# ZB3.net
KiCad netlist of a schematic drawn in Altium Designer
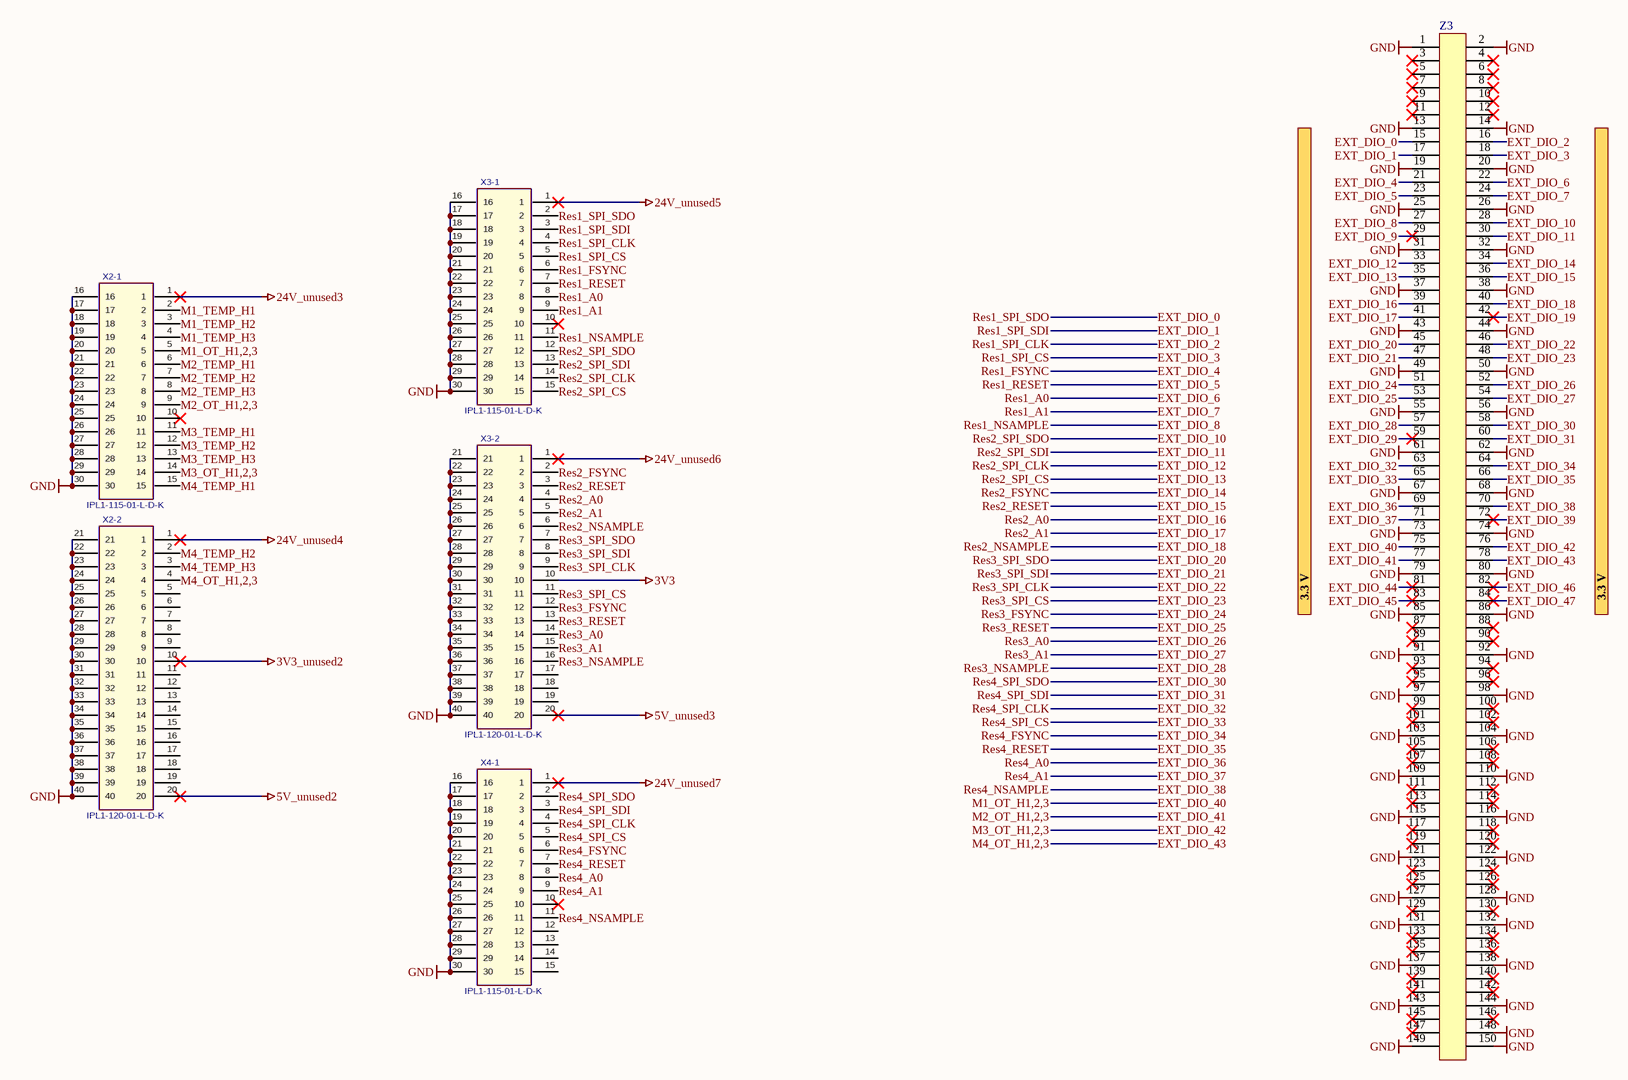
[diagram p0: ZB3.SchDoc]

(export (version "E")
  (design (tool "Eeschema 10.0.6"))
  (components
    (comp (ref "X2-1")
      (value "IPL1-115-01-L-D-K")
      (footprint "IPL1-115-01-YYY-D-K")
      (description "2.54 mm Double Row Terminal Assembly")
      (fields
        (field (name "MANUFACTURER") "SAMTEC")
        (field (name "LCSC PART NUMBER") "C17431809")
        (field (name "CREATED FROM") "MGremer")
      )
      (libsource (lib "user") (part "IPL1-115-01-XX-D-XX"))
    )
    (comp (ref "X2-2")
      (value "IPL1-120-01-L-D-K")
      (footprint "SAMTEC_IPL1-120-01-X-D-K")
      (description "Terminal Assembly, Double Row, Thru-Hole, 2.54 mm x 2.54 mm Pitch, 40 Pins")
      (fields
        (field (name "MANUFACTURER") "SAMTEC")
        (field (name "LCSC PART NUMBER") "C17429670")
        (field (name "CREATED FROM") "PBaumann")
      )
      (libsource (lib "user") (part "IPL1-120-01-XX-D-XX"))
    )
    (comp (ref "X3-1")
      (value "IPL1-115-01-L-D-K")
      (footprint "IPL1-115-01-YYY-D-K")
      (description "2.54 mm Double Row Terminal Assembly")
      (fields
        (field (name "MANUFACTURER") "SAMTEC")
        (field (name "LCSC PART NUMBER") "C17431809")
        (field (name "CREATED FROM") "MGremer")
      )
      (libsource (lib "user") (part "IPL1-115-01-XX-D-XX"))
    )
    (comp (ref "X3-2")
      (value "IPL1-120-01-L-D-K")
      (footprint "SAMTEC_IPL1-120-01-X-D-K")
      (description "Terminal Assembly, Double Row, Thru-Hole, 2.54 mm x 2.54 mm Pitch, 40 Pins")
      (fields
        (field (name "MANUFACTURER") "SAMTEC")
        (field (name "LCSC PART NUMBER") "C17429670")
        (field (name "CREATED FROM") "PBaumann")
      )
      (libsource (lib "user") (part "IPL1-120-01-XX-D-XX"))
    )
    (comp (ref "X4-1")
      (value "IPL1-115-01-L-D-K")
      (footprint "IPL1-115-01-YYY-D-K")
      (description "2.54 mm Double Row Terminal Assembly")
      (fields
        (field (name "MANUFACTURER") "SAMTEC")
        (field (name "LCSC PART NUMBER") "C17431809")
        (field (name "CREATED FROM") "MGremer")
      )
      (libsource (lib "user") (part "IPL1-115-01-XX-D-XX"))
    )
    (comp (ref "Z3")
      (value "~")
      (footprint "ERM8-075-02.0-L-DV")
      (description "0.80 mm Edge Rate Rugged High Speed")
      (fields
        (field (name "MANUFACTURER PART NUMBER") "ERM8-075-02.0-L-DV-TR")
        (field (name "MANUFACTURER") "SAMTEC")
        (field (name "CREATED FROM") "AGeiger")
      )
      (libsource (lib "user") (part "CON-150"))
    )
  )
  (nets
    (net (code "1") (name "/EXT_DIO_0") (class "Default")
      (node (ref "X3-1") (pin "2") (pinfunction "2_2") (pintype "passive"))
      (node (ref "Z3") (pin "15") (pinfunction "15_15") (pintype "passive"))
    )
    (net (code "2") (name "/EXT_DIO_1") (class "Default")
      (node (ref "X3-1") (pin "3") (pinfunction "3_3") (pintype "passive"))
      (node (ref "Z3") (pin "17") (pinfunction "17_17") (pintype "passive"))
    )
    (net (code "3") (name "/EXT_DIO_2") (class "Default")
      (node (ref "X3-1") (pin "4") (pinfunction "4_4") (pintype "passive"))
      (node (ref "Z3") (pin "16") (pinfunction "16_16") (pintype "passive"))
    )
    (net (code "4") (name "/EXT_DIO_3") (class "Default")
      (node (ref "X3-1") (pin "5") (pinfunction "5_5") (pintype "passive"))
      (node (ref "Z3") (pin "18") (pinfunction "18_18") (pintype "passive"))
    )
    (net (code "5") (name "/EXT_DIO_4") (class "Default")
      (node (ref "X3-1") (pin "6") (pinfunction "6_6") (pintype "passive"))
      (node (ref "Z3") (pin "21") (pinfunction "21_21") (pintype "passive"))
    )
    (net (code "6") (name "/EXT_DIO_5") (class "Default")
      (node (ref "X3-1") (pin "7") (pinfunction "7_7") (pintype "passive"))
      (node (ref "Z3") (pin "23") (pinfunction "23_23") (pintype "passive"))
    )
    (net (code "7") (name "/EXT_DIO_6") (class "Default")
      (node (ref "X3-1") (pin "8") (pinfunction "8_8") (pintype "passive"))
      (node (ref "Z3") (pin "22") (pinfunction "22_22") (pintype "passive"))
    )
    (net (code "8") (name "/EXT_DIO_7") (class "Default")
      (node (ref "X3-1") (pin "9") (pinfunction "9_9") (pintype "passive"))
      (node (ref "Z3") (pin "24") (pinfunction "24_24") (pintype "passive"))
    )
    (net (code "9") (name "/EXT_DIO_8") (class "Default")
      (node (ref "X3-1") (pin "11") (pinfunction "11_11") (pintype "passive"))
      (node (ref "Z3") (pin "27") (pinfunction "27_27") (pintype "passive"))
    )
    (net (code "10") (name "/EXT_DIO_9") (class "Default")
      (node (ref "Z3") (pin "29") (pinfunction "29_29") (pintype "passive+no_connect"))
    )
    (net (code "11") (name "/EXT_DIO_10") (class "Default")
      (node (ref "X3-1") (pin "12") (pinfunction "12_12") (pintype "passive"))
      (node (ref "Z3") (pin "28") (pinfunction "28_28") (pintype "passive"))
    )
    (net (code "12") (name "/EXT_DIO_11") (class "Default")
      (node (ref "X3-1") (pin "13") (pinfunction "13_13") (pintype "passive"))
      (node (ref "Z3") (pin "30") (pinfunction "30_30") (pintype "passive"))
    )
    (net (code "13") (name "/EXT_DIO_12") (class "Default")
      (node (ref "X3-1") (pin "14") (pinfunction "14_14") (pintype "passive"))
      (node (ref "Z3") (pin "33") (pinfunction "33_33") (pintype "passive"))
    )
    (net (code "14") (name "/EXT_DIO_13") (class "Default")
      (node (ref "X3-1") (pin "15") (pinfunction "15_15") (pintype "passive"))
      (node (ref "Z3") (pin "35") (pinfunction "35_35") (pintype "passive"))
    )
    (net (code "15") (name "/EXT_DIO_14") (class "Default")
      (node (ref "X3-2") (pin "2") (pinfunction "2_2") (pintype "passive"))
      (node (ref "Z3") (pin "34") (pinfunction "34_34") (pintype "passive"))
    )
    (net (code "16") (name "/EXT_DIO_15") (class "Default")
      (node (ref "X3-2") (pin "3") (pinfunction "3_3") (pintype "passive"))
      (node (ref "Z3") (pin "36") (pinfunction "36_36") (pintype "passive"))
    )
    (net (code "17") (name "/EXT_DIO_16") (class "Default")
      (node (ref "X3-2") (pin "4") (pinfunction "4_4") (pintype "passive"))
      (node (ref "Z3") (pin "39") (pinfunction "39_39") (pintype "passive"))
    )
    (net (code "18") (name "/EXT_DIO_17") (class "Default")
      (node (ref "X3-2") (pin "5") (pinfunction "5_5") (pintype "passive"))
      (node (ref "Z3") (pin "41") (pinfunction "41_41") (pintype "passive"))
    )
    (net (code "19") (name "/EXT_DIO_18") (class "Default")
      (node (ref "X3-2") (pin "6") (pinfunction "6_6") (pintype "passive"))
      (node (ref "Z3") (pin "40") (pinfunction "40_40") (pintype "passive"))
    )
    (net (code "20") (name "/EXT_DIO_19") (class "Default")
      (node (ref "Z3") (pin "42") (pinfunction "42_42") (pintype "passive+no_connect"))
    )
    (net (code "21") (name "/EXT_DIO_20") (class "Default")
      (node (ref "X3-2") (pin "7") (pinfunction "7_7") (pintype "passive"))
      (node (ref "Z3") (pin "45") (pinfunction "45_45") (pintype "passive"))
    )
    (net (code "22") (name "/EXT_DIO_21") (class "Default")
      (node (ref "X3-2") (pin "8") (pinfunction "8_8") (pintype "passive"))
      (node (ref "Z3") (pin "47") (pinfunction "47_47") (pintype "passive"))
    )
    (net (code "23") (name "/EXT_DIO_22") (class "Default")
      (node (ref "X3-2") (pin "9") (pinfunction "9_9") (pintype "passive"))
      (node (ref "Z3") (pin "46") (pinfunction "46_46") (pintype "passive"))
    )
    (net (code "24") (name "/EXT_DIO_23") (class "Default")
      (node (ref "X3-2") (pin "11") (pinfunction "11_11") (pintype "passive"))
      (node (ref "Z3") (pin "48") (pinfunction "48_48") (pintype "passive"))
    )
    (net (code "25") (name "/EXT_DIO_24") (class "Default")
      (node (ref "X3-2") (pin "12") (pinfunction "12_12") (pintype "passive"))
      (node (ref "Z3") (pin "51") (pinfunction "51_51") (pintype "passive"))
    )
    (net (code "26") (name "/EXT_DIO_25") (class "Default")
      (node (ref "X3-2") (pin "13") (pinfunction "13_13") (pintype "passive"))
      (node (ref "Z3") (pin "53") (pinfunction "53_53") (pintype "passive"))
    )
    (net (code "27") (name "/EXT_DIO_26") (class "Default")
      (node (ref "X3-2") (pin "14") (pinfunction "14_14") (pintype "passive"))
      (node (ref "Z3") (pin "52") (pinfunction "52_52") (pintype "passive"))
    )
    (net (code "28") (name "/EXT_DIO_27") (class "Default")
      (node (ref "X3-2") (pin "15") (pinfunction "15_15") (pintype "passive"))
      (node (ref "Z3") (pin "54") (pinfunction "54_54") (pintype "passive"))
    )
    (net (code "29") (name "/EXT_DIO_28") (class "Default")
      (node (ref "X3-2") (pin "16") (pinfunction "16_16") (pintype "passive"))
      (node (ref "Z3") (pin "57") (pinfunction "57_57") (pintype "passive"))
    )
    (net (code "30") (name "/EXT_DIO_29") (class "Default")
      (node (ref "Z3") (pin "59") (pinfunction "59_59") (pintype "passive+no_connect"))
    )
    (net (code "31") (name "/EXT_DIO_30") (class "Default")
      (node (ref "X4-1") (pin "2") (pinfunction "2_2") (pintype "passive"))
      (node (ref "Z3") (pin "58") (pinfunction "58_58") (pintype "passive"))
    )
    (net (code "32") (name "/EXT_DIO_31") (class "Default")
      (node (ref "X4-1") (pin "3") (pinfunction "3_3") (pintype "passive"))
      (node (ref "Z3") (pin "60") (pinfunction "60_60") (pintype "passive"))
    )
    (net (code "33") (name "/EXT_DIO_32") (class "Default")
      (node (ref "X4-1") (pin "4") (pinfunction "4_4") (pintype "passive"))
      (node (ref "Z3") (pin "63") (pinfunction "63_63") (pintype "passive"))
    )
    (net (code "34") (name "/EXT_DIO_33") (class "Default")
      (node (ref "X4-1") (pin "5") (pinfunction "5_5") (pintype "passive"))
      (node (ref "Z3") (pin "65") (pinfunction "65_65") (pintype "passive"))
    )
    (net (code "35") (name "/EXT_DIO_34") (class "Default")
      (node (ref "X4-1") (pin "6") (pinfunction "6_6") (pintype "passive"))
      (node (ref "Z3") (pin "64") (pinfunction "64_64") (pintype "passive"))
    )
    (net (code "36") (name "/EXT_DIO_35") (class "Default")
      (node (ref "X4-1") (pin "7") (pinfunction "7_7") (pintype "passive"))
      (node (ref "Z3") (pin "66") (pinfunction "66_66") (pintype "passive"))
    )
    (net (code "37") (name "/EXT_DIO_36") (class "Default")
      (node (ref "X4-1") (pin "8") (pinfunction "8_8") (pintype "passive"))
      (node (ref "Z3") (pin "69") (pinfunction "69_69") (pintype "passive"))
    )
    (net (code "38") (name "/EXT_DIO_37") (class "Default")
      (node (ref "X4-1") (pin "9") (pinfunction "9_9") (pintype "passive"))
      (node (ref "Z3") (pin "71") (pinfunction "71_71") (pintype "passive"))
    )
    (net (code "39") (name "/EXT_DIO_38") (class "Default")
      (node (ref "X4-1") (pin "11") (pinfunction "11_11") (pintype "passive"))
      (node (ref "Z3") (pin "70") (pinfunction "70_70") (pintype "passive"))
    )
    (net (code "40") (name "/EXT_DIO_39") (class "Default")
      (node (ref "Z3") (pin "72") (pinfunction "72_72") (pintype "passive+no_connect"))
    )
    (net (code "41") (name "/EXT_DIO_40") (class "Default")
      (node (ref "X2-1") (pin "5") (pinfunction "5_5") (pintype "passive"))
      (node (ref "Z3") (pin "75") (pinfunction "75_75") (pintype "passive"))
    )
    (net (code "42") (name "/EXT_DIO_41") (class "Default")
      (node (ref "X2-1") (pin "9") (pinfunction "9_9") (pintype "passive"))
      (node (ref "Z3") (pin "77") (pinfunction "77_77") (pintype "passive"))
    )
    (net (code "43") (name "/EXT_DIO_42") (class "Default")
      (node (ref "X2-1") (pin "14") (pinfunction "14_14") (pintype "passive"))
      (node (ref "Z3") (pin "76") (pinfunction "76_76") (pintype "passive"))
    )
    (net (code "44") (name "/EXT_DIO_43") (class "Default")
      (node (ref "X2-2") (pin "4") (pinfunction "4_4") (pintype "passive"))
      (node (ref "Z3") (pin "78") (pinfunction "78_78") (pintype "passive"))
    )
    (net (code "45") (name "/EXT_DIO_44") (class "Default")
      (node (ref "Z3") (pin "81") (pinfunction "81_81") (pintype "passive+no_connect"))
    )
    (net (code "46") (name "/EXT_DIO_45") (class "Default")
      (node (ref "Z3") (pin "83") (pinfunction "83_83") (pintype "passive+no_connect"))
    )
    (net (code "47") (name "/EXT_DIO_46") (class "Default")
      (node (ref "Z3") (pin "82") (pinfunction "82_82") (pintype "passive+no_connect"))
    )
    (net (code "48") (name "/EXT_DIO_47") (class "Default")
      (node (ref "Z3") (pin "84") (pinfunction "84_84") (pintype "passive+no_connect"))
    )
    (net (code "49") (name "/M1_TEMP_H1") (class "Default")
      (node (ref "X2-1") (pin "2") (pinfunction "2_2") (pintype "passive"))
    )
    (net (code "50") (name "/M1_TEMP_H2") (class "Default")
      (node (ref "X2-1") (pin "3") (pinfunction "3_3") (pintype "passive"))
    )
    (net (code "51") (name "/M1_TEMP_H3") (class "Default")
      (node (ref "X2-1") (pin "4") (pinfunction "4_4") (pintype "passive"))
    )
    (net (code "52") (name "/M2_TEMP_H1") (class "Default")
      (node (ref "X2-1") (pin "6") (pinfunction "6_6") (pintype "passive"))
    )
    (net (code "53") (name "/M2_TEMP_H2") (class "Default")
      (node (ref "X2-1") (pin "7") (pinfunction "7_7") (pintype "passive"))
    )
    (net (code "54") (name "/M2_TEMP_H3") (class "Default")
      (node (ref "X2-1") (pin "8") (pinfunction "8_8") (pintype "passive"))
    )
    (net (code "55") (name "/M3_TEMP_H1") (class "Default")
      (node (ref "X2-1") (pin "11") (pinfunction "11_11") (pintype "passive"))
    )
    (net (code "56") (name "/M3_TEMP_H2") (class "Default")
      (node (ref "X2-1") (pin "12") (pinfunction "12_12") (pintype "passive"))
    )
    (net (code "57") (name "/M3_TEMP_H3") (class "Default")
      (node (ref "X2-1") (pin "13") (pinfunction "13_13") (pintype "passive"))
    )
    (net (code "58") (name "/M4_TEMP_H1") (class "Default")
      (node (ref "X2-1") (pin "15") (pinfunction "15_15") (pintype "passive"))
    )
    (net (code "59") (name "/M4_TEMP_H2") (class "Default")
      (node (ref "X2-2") (pin "2") (pinfunction "2_2") (pintype "passive"))
    )
    (net (code "60") (name "/M4_TEMP_H3") (class "Default")
      (node (ref "X2-2") (pin "3") (pinfunction "3_3") (pintype "passive"))
    )
    (net (code "61") (name "3V3") (class "Default")
      (node (ref "X3-2") (pin "10") (pinfunction "10_10") (pintype "passive"))
    )
    (net (code "62") (name "3V3_unused2") (class "Default")
      (node (ref "X2-2") (pin "10") (pinfunction "10_10") (pintype "passive"))
    )
    (net (code "63") (name "5V_unused2") (class "Default")
      (node (ref "X2-2") (pin "20") (pinfunction "20_20") (pintype "passive"))
    )
    (net (code "64") (name "5V_unused3") (class "Default")
      (node (ref "X3-2") (pin "20") (pinfunction "20_20") (pintype "passive"))
    )
    (net (code "65") (name "24V_unused3") (class "Default")
      (node (ref "X2-1") (pin "1") (pinfunction "1_1") (pintype "passive"))
    )
    (net (code "66") (name "24V_unused4") (class "Default")
      (node (ref "X2-2") (pin "1") (pinfunction "1_1") (pintype "passive"))
    )
    (net (code "67") (name "24V_unused5") (class "Default")
      (node (ref "X3-1") (pin "1") (pinfunction "1_1") (pintype "passive"))
    )
    (net (code "68") (name "24V_unused6") (class "Default")
      (node (ref "X3-2") (pin "1") (pinfunction "1_1") (pintype "passive"))
    )
    (net (code "69") (name "24V_unused7") (class "Default")
      (node (ref "X4-1") (pin "1") (pinfunction "1_1") (pintype "passive"))
    )
    (net (code "70") (name "GND") (class "Default")
      (node (ref "X2-1") (pin "16") (pinfunction "16_16") (pintype "passive"))
      (node (ref "X2-1") (pin "17") (pinfunction "17_17") (pintype "passive"))
      (node (ref "X2-1") (pin "18") (pinfunction "18_18") (pintype "passive"))
      (node (ref "X2-1") (pin "19") (pinfunction "19_19") (pintype "passive"))
      (node (ref "X2-1") (pin "20") (pinfunction "20_20") (pintype "passive"))
      (node (ref "X2-1") (pin "21") (pinfunction "21_21") (pintype "passive"))
      (node (ref "X2-1") (pin "22") (pinfunction "22_22") (pintype "passive"))
      (node (ref "X2-1") (pin "23") (pinfunction "23_23") (pintype "passive"))
      (node (ref "X2-1") (pin "24") (pinfunction "24_24") (pintype "passive"))
      (node (ref "X2-1") (pin "25") (pinfunction "25_25") (pintype "passive"))
      (node (ref "X2-1") (pin "26") (pinfunction "26_26") (pintype "passive"))
      (node (ref "X2-1") (pin "27") (pinfunction "27_27") (pintype "passive"))
      (node (ref "X2-1") (pin "28") (pinfunction "28_28") (pintype "passive"))
      (node (ref "X2-1") (pin "29") (pinfunction "29_29") (pintype "passive"))
      (node (ref "X2-1") (pin "30") (pinfunction "30_30") (pintype "passive"))
      (node (ref "X2-2") (pin "21") (pinfunction "21_21") (pintype "passive"))
      (node (ref "X2-2") (pin "22") (pinfunction "22_22") (pintype "passive"))
      (node (ref "X2-2") (pin "23") (pinfunction "23_23") (pintype "passive"))
      (node (ref "X2-2") (pin "24") (pinfunction "24_24") (pintype "passive"))
      (node (ref "X2-2") (pin "25") (pinfunction "25_25") (pintype "passive"))
      (node (ref "X2-2") (pin "26") (pinfunction "26_26") (pintype "passive"))
      (node (ref "X2-2") (pin "27") (pinfunction "27_27") (pintype "passive"))
      (node (ref "X2-2") (pin "28") (pinfunction "28_28") (pintype "passive"))
      (node (ref "X2-2") (pin "29") (pinfunction "29_29") (pintype "passive"))
      (node (ref "X2-2") (pin "30") (pinfunction "30_30") (pintype "passive"))
      (node (ref "X2-2") (pin "31") (pinfunction "31_31") (pintype "passive"))
      (node (ref "X2-2") (pin "32") (pinfunction "32_32") (pintype "passive"))
      (node (ref "X2-2") (pin "33") (pinfunction "33_33") (pintype "passive"))
      (node (ref "X2-2") (pin "34") (pinfunction "34_34") (pintype "passive"))
      (node (ref "X2-2") (pin "35") (pinfunction "35_35") (pintype "passive"))
      (node (ref "X2-2") (pin "36") (pinfunction "36_36") (pintype "passive"))
      (node (ref "X2-2") (pin "37") (pinfunction "37_37") (pintype "passive"))
      (node (ref "X2-2") (pin "38") (pinfunction "38_38") (pintype "passive"))
      (node (ref "X2-2") (pin "39") (pinfunction "39_39") (pintype "passive"))
      (node (ref "X2-2") (pin "40") (pinfunction "40_40") (pintype "passive"))
      (node (ref "X3-1") (pin "16") (pinfunction "16_16") (pintype "passive"))
      (node (ref "X3-1") (pin "17") (pinfunction "17_17") (pintype "passive"))
      (node (ref "X3-1") (pin "18") (pinfunction "18_18") (pintype "passive"))
      (node (ref "X3-1") (pin "19") (pinfunction "19_19") (pintype "passive"))
      (node (ref "X3-1") (pin "20") (pinfunction "20_20") (pintype "passive"))
      (node (ref "X3-1") (pin "21") (pinfunction "21_21") (pintype "passive"))
      (node (ref "X3-1") (pin "22") (pinfunction "22_22") (pintype "passive"))
      (node (ref "X3-1") (pin "23") (pinfunction "23_23") (pintype "passive"))
      (node (ref "X3-1") (pin "24") (pinfunction "24_24") (pintype "passive"))
      (node (ref "X3-1") (pin "25") (pinfunction "25_25") (pintype "passive"))
      (node (ref "X3-1") (pin "26") (pinfunction "26_26") (pintype "passive"))
      (node (ref "X3-1") (pin "27") (pinfunction "27_27") (pintype "passive"))
      (node (ref "X3-1") (pin "28") (pinfunction "28_28") (pintype "passive"))
      (node (ref "X3-1") (pin "29") (pinfunction "29_29") (pintype "passive"))
      (node (ref "X3-1") (pin "30") (pinfunction "30_30") (pintype "passive"))
      (node (ref "X3-2") (pin "21") (pinfunction "21_21") (pintype "passive"))
      (node (ref "X3-2") (pin "22") (pinfunction "22_22") (pintype "passive"))
      (node (ref "X3-2") (pin "23") (pinfunction "23_23") (pintype "passive"))
      (node (ref "X3-2") (pin "24") (pinfunction "24_24") (pintype "passive"))
      (node (ref "X3-2") (pin "25") (pinfunction "25_25") (pintype "passive"))
      (node (ref "X3-2") (pin "26") (pinfunction "26_26") (pintype "passive"))
      (node (ref "X3-2") (pin "27") (pinfunction "27_27") (pintype "passive"))
      (node (ref "X3-2") (pin "28") (pinfunction "28_28") (pintype "passive"))
      (node (ref "X3-2") (pin "29") (pinfunction "29_29") (pintype "passive"))
      (node (ref "X3-2") (pin "30") (pinfunction "30_30") (pintype "passive"))
      (node (ref "X3-2") (pin "31") (pinfunction "31_31") (pintype "passive"))
      (node (ref "X3-2") (pin "32") (pinfunction "32_32") (pintype "passive"))
      (node (ref "X3-2") (pin "33") (pinfunction "33_33") (pintype "passive"))
      (node (ref "X3-2") (pin "34") (pinfunction "34_34") (pintype "passive"))
      (node (ref "X3-2") (pin "35") (pinfunction "35_35") (pintype "passive"))
      (node (ref "X3-2") (pin "36") (pinfunction "36_36") (pintype "passive"))
      (node (ref "X3-2") (pin "37") (pinfunction "37_37") (pintype "passive"))
      (node (ref "X3-2") (pin "38") (pinfunction "38_38") (pintype "passive"))
      (node (ref "X3-2") (pin "39") (pinfunction "39_39") (pintype "passive"))
      (node (ref "X3-2") (pin "40") (pinfunction "40_40") (pintype "passive"))
      (node (ref "X4-1") (pin "16") (pinfunction "16_16") (pintype "passive"))
      (node (ref "X4-1") (pin "17") (pinfunction "17_17") (pintype "passive"))
      (node (ref "X4-1") (pin "18") (pinfunction "18_18") (pintype "passive"))
      (node (ref "X4-1") (pin "19") (pinfunction "19_19") (pintype "passive"))
      (node (ref "X4-1") (pin "20") (pinfunction "20_20") (pintype "passive"))
      (node (ref "X4-1") (pin "21") (pinfunction "21_21") (pintype "passive"))
      (node (ref "X4-1") (pin "22") (pinfunction "22_22") (pintype "passive"))
      (node (ref "X4-1") (pin "23") (pinfunction "23_23") (pintype "passive"))
      (node (ref "X4-1") (pin "24") (pinfunction "24_24") (pintype "passive"))
      (node (ref "X4-1") (pin "25") (pinfunction "25_25") (pintype "passive"))
      (node (ref "X4-1") (pin "26") (pinfunction "26_26") (pintype "passive"))
      (node (ref "X4-1") (pin "27") (pinfunction "27_27") (pintype "passive"))
      (node (ref "X4-1") (pin "28") (pinfunction "28_28") (pintype "passive"))
      (node (ref "X4-1") (pin "29") (pinfunction "29_29") (pintype "passive"))
      (node (ref "X4-1") (pin "30") (pinfunction "30_30") (pintype "passive"))
      (node (ref "Z3") (pin "1") (pinfunction "1_1") (pintype "passive"))
      (node (ref "Z3") (pin "103") (pinfunction "103_103") (pintype "passive"))
      (node (ref "Z3") (pin "104") (pinfunction "104_104") (pintype "passive"))
      (node (ref "Z3") (pin "109") (pinfunction "109_109") (pintype "passive"))
      (node (ref "Z3") (pin "110") (pinfunction "110_110") (pintype "passive"))
      (node (ref "Z3") (pin "115") (pinfunction "115_115") (pintype "passive"))
      (node (ref "Z3") (pin "116") (pinfunction "116_116") (pintype "passive"))
      (node (ref "Z3") (pin "121") (pinfunction "121_121") (pintype "passive"))
      (node (ref "Z3") (pin "122") (pinfunction "122_122") (pintype "passive"))
      (node (ref "Z3") (pin "127") (pinfunction "127_127") (pintype "passive"))
      (node (ref "Z3") (pin "128") (pinfunction "128_128") (pintype "passive"))
      (node (ref "Z3") (pin "13") (pinfunction "13_13") (pintype "passive"))
      (node (ref "Z3") (pin "131") (pinfunction "131_131") (pintype "passive"))
      (node (ref "Z3") (pin "132") (pinfunction "132_132") (pintype "passive"))
      (node (ref "Z3") (pin "137") (pinfunction "137_137") (pintype "passive"))
      (node (ref "Z3") (pin "138") (pinfunction "138_138") (pintype "passive"))
      (node (ref "Z3") (pin "14") (pinfunction "14_14") (pintype "passive"))
      (node (ref "Z3") (pin "143") (pinfunction "143_143") (pintype "passive"))
      (node (ref "Z3") (pin "144") (pinfunction "144_144") (pintype "passive"))
      (node (ref "Z3") (pin "148") (pinfunction "148_148") (pintype "passive"))
      (node (ref "Z3") (pin "149") (pinfunction "149_149") (pintype "passive"))
      (node (ref "Z3") (pin "150") (pinfunction "150_150") (pintype "passive"))
      (node (ref "Z3") (pin "19") (pinfunction "19_19") (pintype "passive"))
      (node (ref "Z3") (pin "2") (pinfunction "2_2") (pintype "passive"))
      (node (ref "Z3") (pin "20") (pinfunction "20_20") (pintype "passive"))
      (node (ref "Z3") (pin "25") (pinfunction "25_25") (pintype "passive"))
      (node (ref "Z3") (pin "26") (pinfunction "26_26") (pintype "passive"))
      (node (ref "Z3") (pin "31") (pinfunction "31_31") (pintype "passive"))
      (node (ref "Z3") (pin "32") (pinfunction "32_32") (pintype "passive"))
      (node (ref "Z3") (pin "37") (pinfunction "37_37") (pintype "passive"))
      (node (ref "Z3") (pin "38") (pinfunction "38_38") (pintype "passive"))
      (node (ref "Z3") (pin "43") (pinfunction "43_43") (pintype "passive"))
      (node (ref "Z3") (pin "44") (pinfunction "44_44") (pintype "passive"))
      (node (ref "Z3") (pin "49") (pinfunction "49_49") (pintype "passive"))
      (node (ref "Z3") (pin "50") (pinfunction "50_50") (pintype "passive"))
      (node (ref "Z3") (pin "55") (pinfunction "55_55") (pintype "passive"))
      (node (ref "Z3") (pin "56") (pinfunction "56_56") (pintype "passive"))
      (node (ref "Z3") (pin "61") (pinfunction "61_61") (pintype "passive"))
      (node (ref "Z3") (pin "62") (pinfunction "62_62") (pintype "passive"))
      (node (ref "Z3") (pin "67") (pinfunction "67_67") (pintype "passive"))
      (node (ref "Z3") (pin "68") (pinfunction "68_68") (pintype "passive"))
      (node (ref "Z3") (pin "73") (pinfunction "73_73") (pintype "passive"))
      (node (ref "Z3") (pin "74") (pinfunction "74_74") (pintype "passive"))
      (node (ref "Z3") (pin "79") (pinfunction "79_79") (pintype "passive"))
      (node (ref "Z3") (pin "80") (pinfunction "80_80") (pintype "passive"))
      (node (ref "Z3") (pin "85") (pinfunction "85_85") (pintype "passive"))
      (node (ref "Z3") (pin "86") (pinfunction "86_86") (pintype "passive"))
      (node (ref "Z3") (pin "91") (pinfunction "91_91") (pintype "passive"))
      (node (ref "Z3") (pin "92") (pinfunction "92_92") (pintype "passive"))
      (node (ref "Z3") (pin "97") (pinfunction "97_97") (pintype "passive"))
      (node (ref "Z3") (pin "98") (pinfunction "98_98") (pintype "passive"))
    )
    (net (code "71") (name "unconnected-(X2-1-Pad10)") (class "Default")
      (node (ref "X2-1") (pin "10") (pinfunction "10_10") (pintype "passive+no_connect"))
    )
    (net (code "72") (name "unconnected-(X2-2-Pad5)") (class "Default")
      (node (ref "X2-2") (pin "5") (pinfunction "5_5") (pintype "passive"))
    )
    (net (code "73") (name "unconnected-(X2-2-Pad6)") (class "Default")
      (node (ref "X2-2") (pin "6") (pinfunction "6_6") (pintype "passive"))
    )
    (net (code "74") (name "unconnected-(X2-2-Pad7)") (class "Default")
      (node (ref "X2-2") (pin "7") (pinfunction "7_7") (pintype "passive"))
    )
    (net (code "75") (name "unconnected-(X2-2-Pad8)") (class "Default")
      (node (ref "X2-2") (pin "8") (pinfunction "8_8") (pintype "passive"))
    )
    (net (code "76") (name "unconnected-(X2-2-Pad9)") (class "Default")
      (node (ref "X2-2") (pin "9") (pinfunction "9_9") (pintype "passive"))
    )
    (net (code "77") (name "unconnected-(X2-2-Pad11)") (class "Default")
      (node (ref "X2-2") (pin "11") (pinfunction "11_11") (pintype "passive"))
    )
    (net (code "78") (name "unconnected-(X2-2-Pad12)") (class "Default")
      (node (ref "X2-2") (pin "12") (pinfunction "12_12") (pintype "passive"))
    )
    (net (code "79") (name "unconnected-(X2-2-Pad13)") (class "Default")
      (node (ref "X2-2") (pin "13") (pinfunction "13_13") (pintype "passive"))
    )
    (net (code "80") (name "unconnected-(X2-2-Pad14)") (class "Default")
      (node (ref "X2-2") (pin "14") (pinfunction "14_14") (pintype "passive"))
    )
    (net (code "81") (name "unconnected-(X2-2-Pad15)") (class "Default")
      (node (ref "X2-2") (pin "15") (pinfunction "15_15") (pintype "passive"))
    )
    (net (code "82") (name "unconnected-(X2-2-Pad16)") (class "Default")
      (node (ref "X2-2") (pin "16") (pinfunction "16_16") (pintype "passive"))
    )
    (net (code "83") (name "unconnected-(X2-2-Pad17)") (class "Default")
      (node (ref "X2-2") (pin "17") (pinfunction "17_17") (pintype "passive"))
    )
    (net (code "84") (name "unconnected-(X2-2-Pad18)") (class "Default")
      (node (ref "X2-2") (pin "18") (pinfunction "18_18") (pintype "passive"))
    )
    (net (code "85") (name "unconnected-(X2-2-Pad19)") (class "Default")
      (node (ref "X2-2") (pin "19") (pinfunction "19_19") (pintype "passive"))
    )
    (net (code "86") (name "unconnected-(X3-1-Pad10)") (class "Default")
      (node (ref "X3-1") (pin "10") (pinfunction "10_10") (pintype "passive+no_connect"))
    )
    (net (code "87") (name "unconnected-(X3-2-Pad17)") (class "Default")
      (node (ref "X3-2") (pin "17") (pinfunction "17_17") (pintype "passive"))
    )
    (net (code "88") (name "unconnected-(X3-2-Pad18)") (class "Default")
      (node (ref "X3-2") (pin "18") (pinfunction "18_18") (pintype "passive"))
    )
    (net (code "89") (name "unconnected-(X3-2-Pad19)") (class "Default")
      (node (ref "X3-2") (pin "19") (pinfunction "19_19") (pintype "passive"))
    )
    (net (code "90") (name "unconnected-(X4-1-Pad10)") (class "Default")
      (node (ref "X4-1") (pin "10") (pinfunction "10_10") (pintype "passive+no_connect"))
    )
    (net (code "91") (name "unconnected-(X4-1-Pad12)") (class "Default")
      (node (ref "X4-1") (pin "12") (pinfunction "12_12") (pintype "passive"))
    )
    (net (code "92") (name "unconnected-(X4-1-Pad13)") (class "Default")
      (node (ref "X4-1") (pin "13") (pinfunction "13_13") (pintype "passive"))
    )
    (net (code "93") (name "unconnected-(X4-1-Pad14)") (class "Default")
      (node (ref "X4-1") (pin "14") (pinfunction "14_14") (pintype "passive"))
    )
    (net (code "94") (name "unconnected-(X4-1-Pad15)") (class "Default")
      (node (ref "X4-1") (pin "15") (pinfunction "15_15") (pintype "passive"))
    )
    (net (code "95") (name "unconnected-(Z3-Pad3)") (class "Default")
      (node (ref "Z3") (pin "3") (pinfunction "3_3") (pintype "passive+no_connect"))
    )
    (net (code "96") (name "unconnected-(Z3-Pad4)") (class "Default")
      (node (ref "Z3") (pin "4") (pinfunction "4_4") (pintype "passive+no_connect"))
    )
    (net (code "97") (name "unconnected-(Z3-Pad5)") (class "Default")
      (node (ref "Z3") (pin "5") (pinfunction "5_5") (pintype "passive+no_connect"))
    )
    (net (code "98") (name "unconnected-(Z3-Pad6)") (class "Default")
      (node (ref "Z3") (pin "6") (pinfunction "6_6") (pintype "passive+no_connect"))
    )
    (net (code "99") (name "unconnected-(Z3-Pad7)") (class "Default")
      (node (ref "Z3") (pin "7") (pinfunction "7_7") (pintype "passive+no_connect"))
    )
    (net (code "100") (name "unconnected-(Z3-Pad8)") (class "Default")
      (node (ref "Z3") (pin "8") (pinfunction "8_8") (pintype "passive+no_connect"))
    )
    (net (code "101") (name "unconnected-(Z3-Pad9)") (class "Default")
      (node (ref "Z3") (pin "9") (pinfunction "9_9") (pintype "passive+no_connect"))
    )
    (net (code "102") (name "unconnected-(Z3-Pad10)") (class "Default")
      (node (ref "Z3") (pin "10") (pinfunction "10_10") (pintype "passive+no_connect"))
    )
    (net (code "103") (name "unconnected-(Z3-Pad11)") (class "Default")
      (node (ref "Z3") (pin "11") (pinfunction "11_11") (pintype "passive+no_connect"))
    )
    (net (code "104") (name "unconnected-(Z3-Pad12)") (class "Default")
      (node (ref "Z3") (pin "12") (pinfunction "12_12") (pintype "passive+no_connect"))
    )
    (net (code "105") (name "unconnected-(Z3-Pad87)") (class "Default")
      (node (ref "Z3") (pin "87") (pinfunction "87_87") (pintype "passive+no_connect"))
    )
    (net (code "106") (name "unconnected-(Z3-Pad88)") (class "Default")
      (node (ref "Z3") (pin "88") (pinfunction "88_88") (pintype "passive+no_connect"))
    )
    (net (code "107") (name "unconnected-(Z3-Pad89)") (class "Default")
      (node (ref "Z3") (pin "89") (pinfunction "89_89") (pintype "passive+no_connect"))
    )
    (net (code "108") (name "unconnected-(Z3-Pad90)") (class "Default")
      (node (ref "Z3") (pin "90") (pinfunction "90_90") (pintype "passive+no_connect"))
    )
    (net (code "109") (name "unconnected-(Z3-Pad93)") (class "Default")
      (node (ref "Z3") (pin "93") (pinfunction "93_93") (pintype "passive+no_connect"))
    )
    (net (code "110") (name "unconnected-(Z3-Pad94)") (class "Default")
      (node (ref "Z3") (pin "94") (pinfunction "94_94") (pintype "passive+no_connect"))
    )
    (net (code "111") (name "unconnected-(Z3-Pad95)") (class "Default")
      (node (ref "Z3") (pin "95") (pinfunction "95_95") (pintype "passive+no_connect"))
    )
    (net (code "112") (name "unconnected-(Z3-Pad96)") (class "Default")
      (node (ref "Z3") (pin "96") (pinfunction "96_96") (pintype "passive+no_connect"))
    )
    (net (code "113") (name "unconnected-(Z3-Pad99)") (class "Default")
      (node (ref "Z3") (pin "99") (pinfunction "99_99") (pintype "passive+no_connect"))
    )
    (net (code "114") (name "unconnected-(Z3-Pad100)") (class "Default")
      (node (ref "Z3") (pin "100") (pinfunction "100_100") (pintype "passive+no_connect"))
    )
    (net (code "115") (name "unconnected-(Z3-Pad101)") (class "Default")
      (node (ref "Z3") (pin "101") (pinfunction "101_101") (pintype "passive+no_connect"))
    )
    (net (code "116") (name "unconnected-(Z3-Pad102)") (class "Default")
      (node (ref "Z3") (pin "102") (pinfunction "102_102") (pintype "passive+no_connect"))
    )
    (net (code "117") (name "unconnected-(Z3-Pad105)") (class "Default")
      (node (ref "Z3") (pin "105") (pinfunction "105_105") (pintype "passive+no_connect"))
    )
    (net (code "118") (name "unconnected-(Z3-Pad106)") (class "Default")
      (node (ref "Z3") (pin "106") (pinfunction "106_106") (pintype "passive+no_connect"))
    )
    (net (code "119") (name "unconnected-(Z3-Pad107)") (class "Default")
      (node (ref "Z3") (pin "107") (pinfunction "107_107") (pintype "passive+no_connect"))
    )
    (net (code "120") (name "unconnected-(Z3-Pad108)") (class "Default")
      (node (ref "Z3") (pin "108") (pinfunction "108_108") (pintype "passive+no_connect"))
    )
    (net (code "121") (name "unconnected-(Z3-Pad111)") (class "Default")
      (node (ref "Z3") (pin "111") (pinfunction "111_111") (pintype "passive+no_connect"))
    )
    (net (code "122") (name "unconnected-(Z3-Pad112)") (class "Default")
      (node (ref "Z3") (pin "112") (pinfunction "112_112") (pintype "passive+no_connect"))
    )
    (net (code "123") (name "unconnected-(Z3-Pad113)") (class "Default")
      (node (ref "Z3") (pin "113") (pinfunction "113_113") (pintype "passive+no_connect"))
    )
    (net (code "124") (name "unconnected-(Z3-Pad114)") (class "Default")
      (node (ref "Z3") (pin "114") (pinfunction "114_114") (pintype "passive+no_connect"))
    )
    (net (code "125") (name "unconnected-(Z3-Pad117)") (class "Default")
      (node (ref "Z3") (pin "117") (pinfunction "117_117") (pintype "passive+no_connect"))
    )
    (net (code "126") (name "unconnected-(Z3-Pad118)") (class "Default")
      (node (ref "Z3") (pin "118") (pinfunction "118_118") (pintype "passive+no_connect"))
    )
    (net (code "127") (name "unconnected-(Z3-Pad119)") (class "Default")
      (node (ref "Z3") (pin "119") (pinfunction "119_119") (pintype "passive+no_connect"))
    )
    (net (code "128") (name "unconnected-(Z3-Pad120)") (class "Default")
      (node (ref "Z3") (pin "120") (pinfunction "120_120") (pintype "passive+no_connect"))
    )
    (net (code "129") (name "unconnected-(Z3-Pad123)") (class "Default")
      (node (ref "Z3") (pin "123") (pinfunction "123_123") (pintype "passive+no_connect"))
    )
    (net (code "130") (name "unconnected-(Z3-Pad124)") (class "Default")
      (node (ref "Z3") (pin "124") (pinfunction "124_124") (pintype "passive+no_connect"))
    )
    (net (code "131") (name "unconnected-(Z3-Pad125)") (class "Default")
      (node (ref "Z3") (pin "125") (pinfunction "125_125") (pintype "passive+no_connect"))
    )
    (net (code "132") (name "unconnected-(Z3-Pad126)") (class "Default")
      (node (ref "Z3") (pin "126") (pinfunction "126_126") (pintype "passive+no_connect"))
    )
    (net (code "133") (name "unconnected-(Z3-Pad129)") (class "Default")
      (node (ref "Z3") (pin "129") (pinfunction "129_129") (pintype "passive+no_connect"))
    )
    (net (code "134") (name "unconnected-(Z3-Pad130)") (class "Default")
      (node (ref "Z3") (pin "130") (pinfunction "130_130") (pintype "passive+no_connect"))
    )
    (net (code "135") (name "unconnected-(Z3-Pad133)") (class "Default")
      (node (ref "Z3") (pin "133") (pinfunction "133_133") (pintype "passive+no_connect"))
    )
    (net (code "136") (name "unconnected-(Z3-Pad134)") (class "Default")
      (node (ref "Z3") (pin "134") (pinfunction "134_134") (pintype "passive+no_connect"))
    )
    (net (code "137") (name "unconnected-(Z3-Pad135)") (class "Default")
      (node (ref "Z3") (pin "135") (pinfunction "135_135") (pintype "passive+no_connect"))
    )
    (net (code "138") (name "unconnected-(Z3-Pad136)") (class "Default")
      (node (ref "Z3") (pin "136") (pinfunction "136_136") (pintype "passive+no_connect"))
    )
    (net (code "139") (name "unconnected-(Z3-Pad139)") (class "Default")
      (node (ref "Z3") (pin "139") (pinfunction "139_139") (pintype "passive+no_connect"))
    )
    (net (code "140") (name "unconnected-(Z3-Pad140)") (class "Default")
      (node (ref "Z3") (pin "140") (pinfunction "140_140") (pintype "passive+no_connect"))
    )
    (net (code "141") (name "unconnected-(Z3-Pad141)") (class "Default")
      (node (ref "Z3") (pin "141") (pinfunction "141_141") (pintype "passive+no_connect"))
    )
    (net (code "142") (name "unconnected-(Z3-Pad142)") (class "Default")
      (node (ref "Z3") (pin "142") (pinfunction "142_142") (pintype "passive+no_connect"))
    )
    (net (code "143") (name "unconnected-(Z3-Pad145)") (class "Default")
      (node (ref "Z3") (pin "145") (pinfunction "145_145") (pintype "passive+no_connect"))
    )
    (net (code "144") (name "unconnected-(Z3-Pad146)") (class "Default")
      (node (ref "Z3") (pin "146") (pinfunction "146_146") (pintype "passive+no_connect"))
    )
    (net (code "145") (name "unconnected-(Z3-Pad147)") (class "Default")
      (node (ref "Z3") (pin "147") (pinfunction "147_147") (pintype "passive+no_connect"))
    )
  )
)
